# SPI-i2c-PWM_--v1.net
KiCad netlist of a schematic drawn in EAGLE
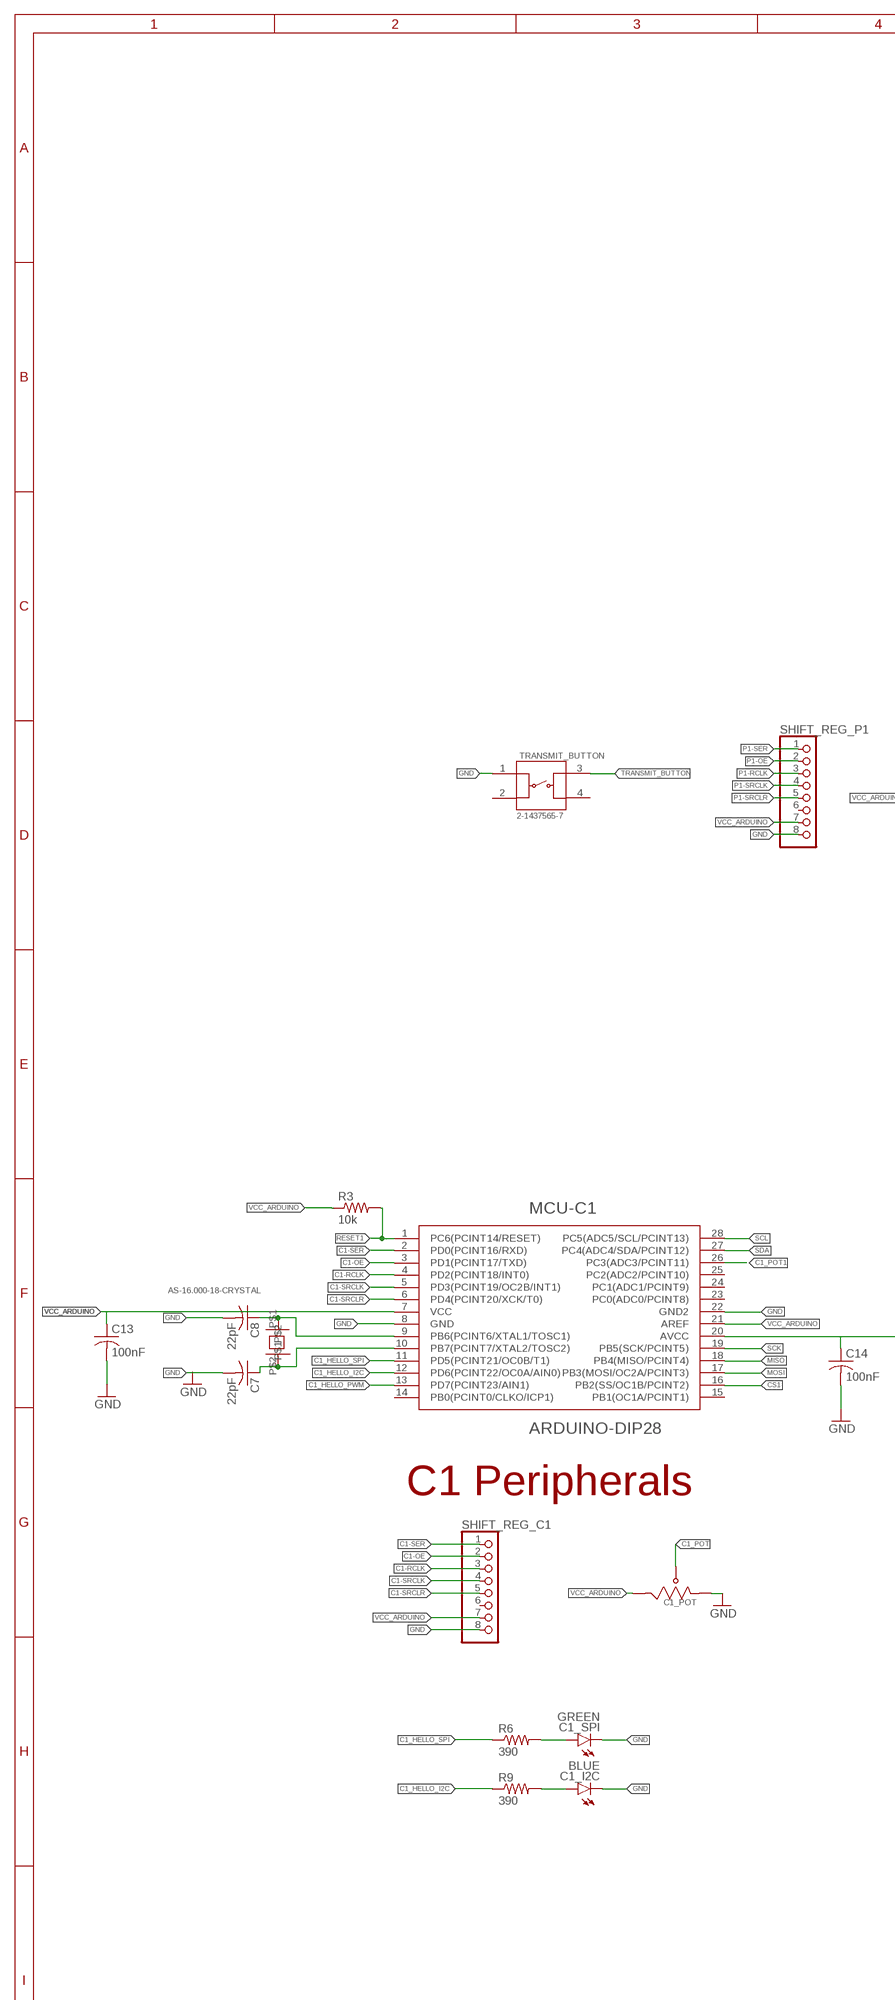
[diagram p0: schematic, sheet 1, part 1 of 2]
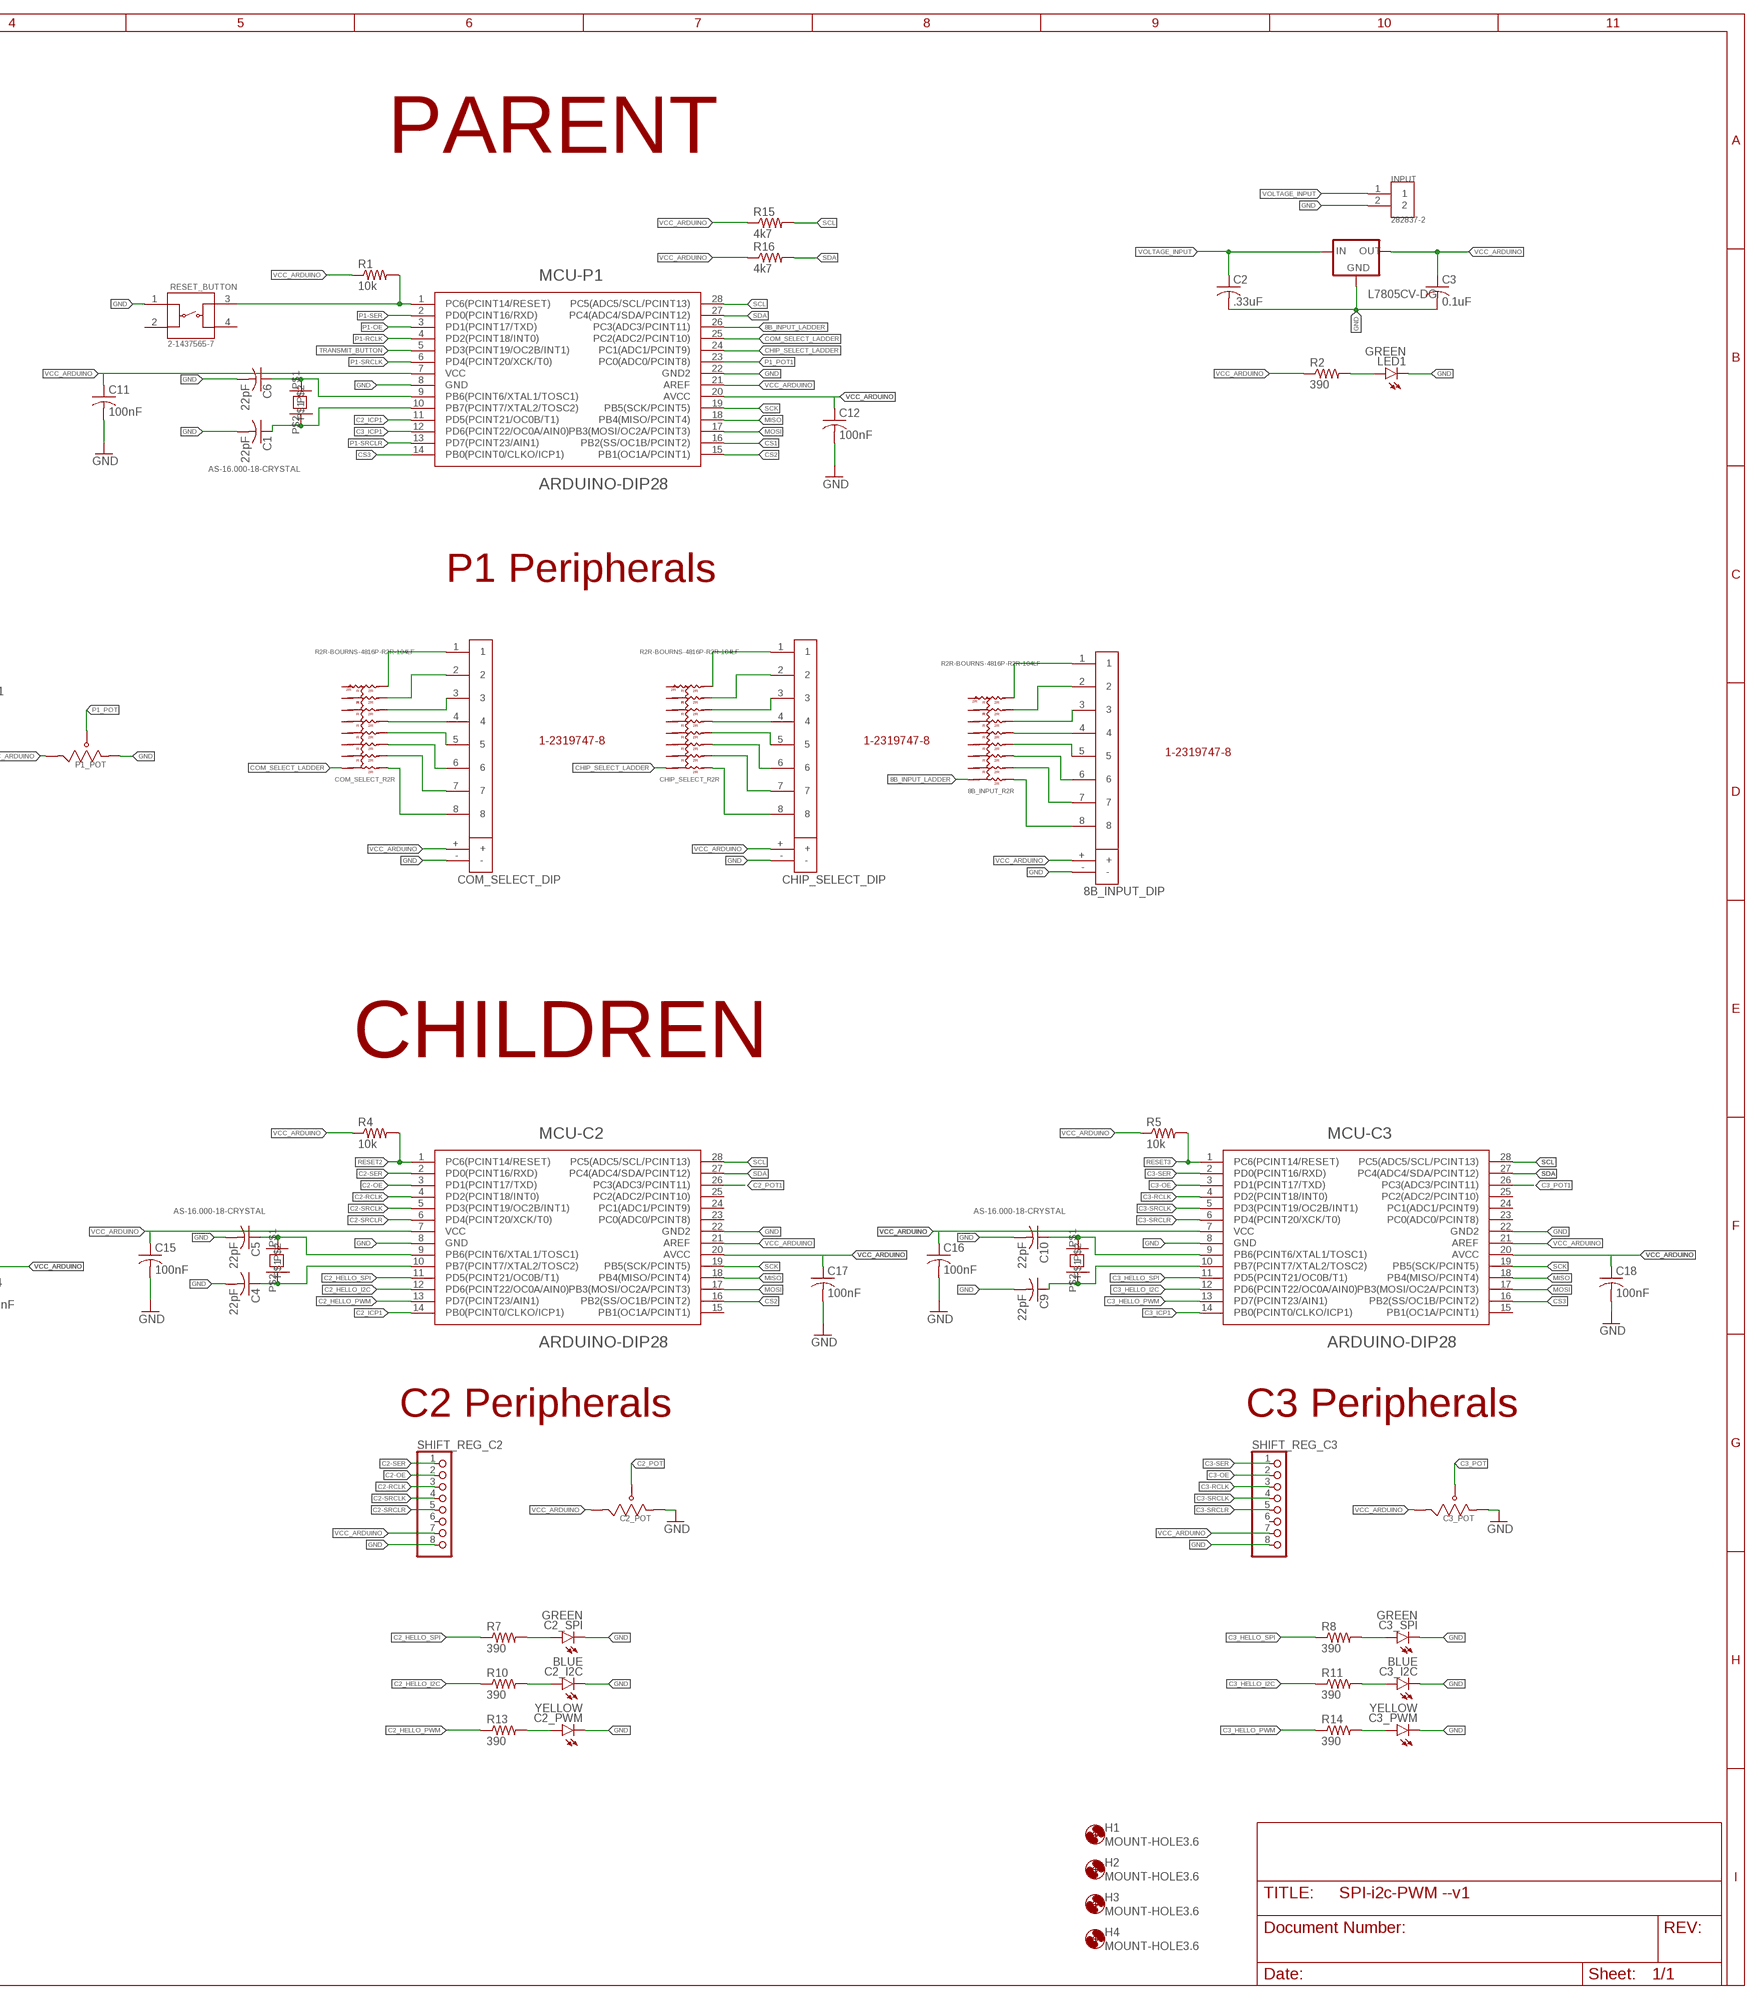
[diagram p1: schematic, sheet 1, part 2 of 2]

(export (version "E")
  (design (tool "Eeschema 10.0.6"))
  (components
    (comp (ref "5V_REG")
      (value "L7805CV-DG")
      (footprint "eagle-import:78XXS")
      (libsource (lib "eagle-import") (part "78XXS"))
    )
    (comp (ref "8B_INPUT_DIP")
      (value "DIP8-TE")
      (footprint "eagle-import:DIP8-TE(1-2319747-8)")
      (libsource (lib "eagle-import") (part "DIP8-TE"))
    )
    (comp (ref "8B_INPUT_R2R")
      (value "R2R-BOURNS-4816P-R2R-104LF")
      (footprint "eagle-import:R2RLADDER")
      (libsource (lib "eagle-import") (part "R2R-BOURNS-4816P-R2R-104LF"))
    )
    (comp (ref "C1")
      (value "22pF")
      (footprint "eagle-import:C0805")
      (libsource (lib "eagle-import") (part "C-USC0805"))
    )
    (comp (ref "C1_I2C")
      (value "BLUE")
      (footprint "eagle-import:CHIP-LED0805")
      (libsource (lib "eagle-import") (part "LEDCHIP-LED0805"))
    )
    (comp (ref "C1_POT")
      (value "POTENTIOMETER-ALLIE")
      (footprint "eagle-import:POT-ALLIEEXPRESS")
      (libsource (lib "eagle-import") (part "POTENTIOMETER-ALLIE"))
    )
    (comp (ref "C1_SPI")
      (value "GREEN")
      (footprint "eagle-import:CHIP-LED0805")
      (libsource (lib "eagle-import") (part "LEDCHIP-LED0805"))
    )
    (comp (ref "C2")
      (value ".33uF")
      (footprint "eagle-import:C0805")
      (libsource (lib "eagle-import") (part "C-USC0805"))
    )
    (comp (ref "C2_I2C")
      (value "BLUE")
      (footprint "eagle-import:CHIP-LED0805")
      (libsource (lib "eagle-import") (part "LEDCHIP-LED0805"))
    )
    (comp (ref "C2_POT")
      (value "POTENTIOMETER-ALLIE")
      (footprint "eagle-import:POT-ALLIEEXPRESS")
      (libsource (lib "eagle-import") (part "POTENTIOMETER-ALLIE"))
    )
    (comp (ref "C2_PWM")
      (value "YELLOW")
      (footprint "eagle-import:CHIP-LED0805")
      (libsource (lib "eagle-import") (part "LEDCHIP-LED0805"))
    )
    (comp (ref "C2_SPI")
      (value "GREEN")
      (footprint "eagle-import:CHIP-LED0805")
      (libsource (lib "eagle-import") (part "LEDCHIP-LED0805"))
    )
    (comp (ref "C3")
      (value "0.1uF")
      (footprint "eagle-import:C0805")
      (libsource (lib "eagle-import") (part "C-USC0805"))
    )
    (comp (ref "C3_I2C")
      (value "BLUE")
      (footprint "eagle-import:CHIP-LED0805")
      (libsource (lib "eagle-import") (part "LEDCHIP-LED0805"))
    )
    (comp (ref "C3_POT")
      (value "POTENTIOMETER-ALLIE")
      (footprint "eagle-import:POT-ALLIEEXPRESS")
      (libsource (lib "eagle-import") (part "POTENTIOMETER-ALLIE"))
    )
    (comp (ref "C3_PWM")
      (value "YELLOW")
      (footprint "eagle-import:CHIP-LED0805")
      (libsource (lib "eagle-import") (part "LEDCHIP-LED0805"))
    )
    (comp (ref "C3_SPI")
      (value "GREEN")
      (footprint "eagle-import:CHIP-LED0805")
      (libsource (lib "eagle-import") (part "LEDCHIP-LED0805"))
    )
    (comp (ref "C4")
      (value "22pF")
      (footprint "eagle-import:C0805")
      (libsource (lib "eagle-import") (part "C-USC0805"))
    )
    (comp (ref "C5")
      (value "22pF")
      (footprint "eagle-import:C0805")
      (libsource (lib "eagle-import") (part "C-USC0805"))
    )
    (comp (ref "C6")
      (value "22pF")
      (footprint "eagle-import:C0805")
      (libsource (lib "eagle-import") (part "C-USC0805"))
    )
    (comp (ref "C7")
      (value "22pF")
      (footprint "eagle-import:C0805")
      (libsource (lib "eagle-import") (part "C-USC0805"))
    )
    (comp (ref "C8")
      (value "22pF")
      (footprint "eagle-import:C0805")
      (libsource (lib "eagle-import") (part "C-USC0805"))
    )
    (comp (ref "C9")
      (value "22pF")
      (footprint "eagle-import:C0805")
      (libsource (lib "eagle-import") (part "C-USC0805"))
    )
    (comp (ref "C10")
      (value "22pF")
      (footprint "eagle-import:C0805")
      (libsource (lib "eagle-import") (part "C-USC0805"))
    )
    (comp (ref "C11")
      (value "100nF")
      (footprint "eagle-import:C0805")
      (libsource (lib "eagle-import") (part "C-USC0805"))
    )
    (comp (ref "C12")
      (value "100nF")
      (footprint "eagle-import:C0805")
      (libsource (lib "eagle-import") (part "C-USC0805"))
    )
    (comp (ref "C13")
      (value "100nF")
      (footprint "eagle-import:C0805")
      (libsource (lib "eagle-import") (part "C-USC0805"))
    )
    (comp (ref "C14")
      (value "100nF")
      (footprint "eagle-import:C0805")
      (libsource (lib "eagle-import") (part "C-USC0805"))
    )
    (comp (ref "C15")
      (value "100nF")
      (footprint "eagle-import:C0805")
      (libsource (lib "eagle-import") (part "C-USC0805"))
    )
    (comp (ref "C16")
      (value "100nF")
      (footprint "eagle-import:C0805")
      (libsource (lib "eagle-import") (part "C-USC0805"))
    )
    (comp (ref "C17")
      (value "100nF")
      (footprint "eagle-import:C0805")
      (libsource (lib "eagle-import") (part "C-USC0805"))
    )
    (comp (ref "C18")
      (value "100nF")
      (footprint "eagle-import:C0805")
      (libsource (lib "eagle-import") (part "C-USC0805"))
    )
    (comp (ref "CHIP_SELECT_DIP")
      (value "DIP8-TE")
      (footprint "eagle-import:DIP8-TE(1-2319747-8)")
      (libsource (lib "eagle-import") (part "DIP8-TE"))
    )
    (comp (ref "CHIP_SELECT_R2R")
      (value "R2R-BOURNS-4816P-R2R-104LF")
      (footprint "eagle-import:R2RLADDER")
      (libsource (lib "eagle-import") (part "R2R-BOURNS-4816P-R2R-104LF"))
    )
    (comp (ref "COM_SELECT_DIP")
      (value "DIP8-TE")
      (footprint "eagle-import:DIP8-TE(1-2319747-8)")
      (libsource (lib "eagle-import") (part "DIP8-TE"))
    )
    (comp (ref "COM_SELECT_R2R")
      (value "R2R-BOURNS-4816P-R2R-104LF")
      (footprint "eagle-import:R2RLADDER")
      (libsource (lib "eagle-import") (part "R2R-BOURNS-4816P-R2R-104LF"))
    )
    (comp (ref "H1")
      (value "MOUNT-HOLE3.6")
      (footprint "eagle-import:3,6")
      (libsource (lib "eagle-import") (part "MOUNT-HOLE3.6"))
    )
    (comp (ref "H2")
      (value "MOUNT-HOLE3.6")
      (footprint "eagle-import:3,6")
      (libsource (lib "eagle-import") (part "MOUNT-HOLE3.6"))
    )
    (comp (ref "H3")
      (value "MOUNT-HOLE3.6")
      (footprint "eagle-import:3,6")
      (libsource (lib "eagle-import") (part "MOUNT-HOLE3.6"))
    )
    (comp (ref "H4")
      (value "MOUNT-HOLE3.6")
      (footprint "eagle-import:3,6")
      (libsource (lib "eagle-import") (part "MOUNT-HOLE3.6"))
    )
    (comp (ref "INPUT")
      (value "282837-2")
      (footprint "eagle-import:TE_282837-2")
      (fields (field (name "MF") "On Shore") (field (name "MP") "OSTTE020104"))
      (libsource (lib "eagle-import") (part "282837-2"))
    )
    (comp (ref "LED1")
      (value "GREEN")
      (footprint "eagle-import:CHIPLED_0805")
      (libsource (lib "eagle-import") (part "LEDCHIPLED_0805"))
    )
    (comp (ref "M1_OSC")
      (value "AS-16.000-18-CRYSTAL")
      (footprint "eagle-import:AS-16.000-18-CRYSTAL")
      (libsource (lib "eagle-import") (part "AS-16.000-18-CRYSTAL"))
    )
    (comp (ref "MCU-C1")
      (value "ARDUINO-DIP28")
      (footprint "eagle-import:DIL28-3")
      (libsource (lib "eagle-import") (part "ARDUINO-DIP28"))
    )
    (comp (ref "MCU-C2")
      (value "ARDUINO-DIP28")
      (footprint "eagle-import:DIL28-3")
      (libsource (lib "eagle-import") (part "ARDUINO-DIP28"))
    )
    (comp (ref "MCU-C3")
      (value "ARDUINO-DIP28")
      (footprint "eagle-import:DIL28-3")
      (libsource (lib "eagle-import") (part "ARDUINO-DIP28"))
    )
    (comp (ref "MCU-P1")
      (value "ARDUINO-DIP28")
      (footprint "eagle-import:DIL28-3")
      (libsource (lib "eagle-import") (part "ARDUINO-DIP28"))
    )
    (comp (ref "P1_POT")
      (value "POTENTIOMETER-ALLIE")
      (footprint "eagle-import:POT-ALLIEEXPRESS")
      (libsource (lib "eagle-import") (part "POTENTIOMETER-ALLIE"))
    )
    (comp (ref "R1")
      (value "10k")
      (footprint "eagle-import:M0805")
      (libsource (lib "eagle-import") (part "R-US_M0805"))
    )
    (comp (ref "R2")
      (value "390")
      (footprint "eagle-import:R0805")
      (libsource (lib "eagle-import") (part "R-US_R0805"))
    )
    (comp (ref "R3")
      (value "10k")
      (footprint "eagle-import:M0805")
      (libsource (lib "eagle-import") (part "R-US_M0805"))
    )
    (comp (ref "R4")
      (value "10k")
      (footprint "eagle-import:M0805")
      (libsource (lib "eagle-import") (part "R-US_M0805"))
    )
    (comp (ref "R5")
      (value "10k")
      (footprint "eagle-import:M0805")
      (libsource (lib "eagle-import") (part "R-US_M0805"))
    )
    (comp (ref "R6")
      (value "390")
      (footprint "eagle-import:M0805")
      (libsource (lib "eagle-import") (part "R-US_M0805"))
    )
    (comp (ref "R7")
      (value "390")
      (footprint "eagle-import:M0805")
      (libsource (lib "eagle-import") (part "R-US_M0805"))
    )
    (comp (ref "R8")
      (value "390")
      (footprint "eagle-import:M0805")
      (libsource (lib "eagle-import") (part "R-US_M0805"))
    )
    (comp (ref "R9")
      (value "390")
      (footprint "eagle-import:M0805")
      (libsource (lib "eagle-import") (part "R-US_M0805"))
    )
    (comp (ref "R10")
      (value "390")
      (footprint "eagle-import:M0805")
      (libsource (lib "eagle-import") (part "R-US_M0805"))
    )
    (comp (ref "R11")
      (value "390")
      (footprint "eagle-import:M0805")
      (libsource (lib "eagle-import") (part "R-US_M0805"))
    )
    (comp (ref "R13")
      (value "390")
      (footprint "eagle-import:M0805")
      (libsource (lib "eagle-import") (part "R-US_M0805"))
    )
    (comp (ref "R14")
      (value "390")
      (footprint "eagle-import:M0805")
      (libsource (lib "eagle-import") (part "R-US_M0805"))
    )
    (comp (ref "R15")
      (value "4k7")
      (footprint "eagle-import:R0805")
      (libsource (lib "eagle-import") (part "R-US_R0805"))
    )
    (comp (ref "R16")
      (value "4k7")
      (footprint "eagle-import:R0805")
      (libsource (lib "eagle-import") (part "R-US_R0805"))
    )
    (comp (ref "RESET_BUTTON")
      (value "2-1437565-7")
      (footprint "eagle-import:SW_2-1437565-7")
      (fields (field (name "MANUFACTURER") "TE Connectivity"))
      (libsource (lib "eagle-import") (part "2-1437565-7"))
    )
    (comp (ref "S1_OSC")
      (value "AS-16.000-18-CRYSTAL")
      (footprint "eagle-import:AS-16.000-18-CRYSTAL")
      (libsource (lib "eagle-import") (part "AS-16.000-18-CRYSTAL"))
    )
    (comp (ref "S2_OSC")
      (value "AS-16.000-18-CRYSTAL")
      (footprint "eagle-import:AS-16.000-18-CRYSTAL")
      (libsource (lib "eagle-import") (part "AS-16.000-18-CRYSTAL"))
    )
    (comp (ref "S3_OSC")
      (value "AS-16.000-18-CRYSTAL")
      (footprint "eagle-import:AS-16.000-18-CRYSTAL")
      (libsource (lib "eagle-import") (part "AS-16.000-18-CRYSTAL"))
    )
    (comp (ref "SHIFT_REG_C1")
      (value "PINHD-1X8")
      (footprint "eagle-import:1X08")
      (libsource (lib "eagle-import") (part "PINHD-1X8"))
    )
    (comp (ref "SHIFT_REG_C2")
      (value "PINHD-1X8")
      (footprint "eagle-import:1X08")
      (libsource (lib "eagle-import") (part "PINHD-1X8"))
    )
    (comp (ref "SHIFT_REG_C3")
      (value "PINHD-1X8")
      (footprint "eagle-import:1X08")
      (libsource (lib "eagle-import") (part "PINHD-1X8"))
    )
    (comp (ref "SHIFT_REG_P1")
      (value "PINHD-1X8")
      (footprint "eagle-import:1X08")
      (libsource (lib "eagle-import") (part "PINHD-1X8"))
    )
    (comp (ref "TRANSMIT_BUTTON")
      (value "2-1437565-7")
      (footprint "eagle-import:SW_2-1437565-7")
      (fields (field (name "MANUFACTURER") "TE Connectivity"))
      (libsource (lib "eagle-import") (part "2-1437565-7"))
    )
  )
  (nets
    (net (code "1") (name "8B_INPUT_LADDER") (class "Default")
      (node (ref "8B_INPUT_R2R") (pin "16") (pinfunction "16_16") (pintype "bidirectional"))
      (node (ref "MCU-P1") (pin "26") (pinfunction "PC3(ADC3/PCINT11)_26") (pintype "bidirectional"))
    )
    (net (code "2") (name "C1-OE") (class "Default")
      (node (ref "MCU-C1") (pin "3") (pinfunction "PD1(PCINT17/TXD)_3") (pintype "bidirectional"))
      (node (ref "SHIFT_REG_C1") (pin "2") (pinfunction "2_2") (pintype "passive"))
    )
    (net (code "3") (name "C1-RCLK") (class "Default")
      (node (ref "MCU-C1") (pin "4") (pinfunction "PD2(PCINT18/INT0)_4") (pintype "bidirectional"))
      (node (ref "SHIFT_REG_C1") (pin "3") (pinfunction "3_3") (pintype "passive"))
    )
    (net (code "4") (name "C1-SER") (class "Default")
      (node (ref "MCU-C1") (pin "2") (pinfunction "PD0(PCINT16/RXD)_2") (pintype "bidirectional"))
      (node (ref "SHIFT_REG_C1") (pin "1") (pinfunction "1_1") (pintype "passive"))
    )
    (net (code "5") (name "C1-SRCLK") (class "Default")
      (node (ref "MCU-C1") (pin "5") (pinfunction "PD3(PCINT19/OC2B/INT1)_5") (pintype "bidirectional"))
      (node (ref "SHIFT_REG_C1") (pin "4") (pinfunction "4_4") (pintype "passive"))
    )
    (net (code "6") (name "C1-SRCLR") (class "Default")
      (node (ref "MCU-C1") (pin "6") (pinfunction "PD4(PCINT20/XCK/T0)_6") (pintype "bidirectional"))
      (node (ref "SHIFT_REG_C1") (pin "5") (pinfunction "5_5") (pintype "passive"))
    )
    (net (code "7") (name "C1_HELLO_I2C") (class "Default")
      (node (ref "MCU-C1") (pin "12") (pinfunction "PD6(PCINT22/OC0A/AIN0)_12") (pintype "bidirectional"))
      (node (ref "R9") (pin "1") (pinfunction "1_1") (pintype "passive"))
    )
    (net (code "8") (name "C1_HELLO_PWM") (class "Default")
      (node (ref "MCU-C1") (pin "13") (pinfunction "PD7(PCINT23/AIN1)_13") (pintype "bidirectional"))
    )
    (net (code "9") (name "C1_HELLO_SPI") (class "Default")
      (node (ref "MCU-C1") (pin "11") (pinfunction "PD5(PCINT21/OC0B/T1)_11") (pintype "bidirectional"))
      (node (ref "R6") (pin "1") (pinfunction "1_1") (pintype "passive"))
    )
    (net (code "10") (name "C1_POT") (class "Default")
      (node (ref "C1_POT") (pin "P$2") (pinfunction "P$2_P$2") (pintype "bidirectional"))
    )
    (net (code "11") (name "C1_POT1") (class "Default")
      (node (ref "MCU-C1") (pin "26") (pinfunction "PC3(ADC3/PCINT11)_26") (pintype "bidirectional"))
    )
    (net (code "12") (name "C2-OE") (class "Default")
      (node (ref "MCU-C2") (pin "3") (pinfunction "PD1(PCINT17/TXD)_3") (pintype "bidirectional"))
      (node (ref "SHIFT_REG_C2") (pin "2") (pinfunction "2_2") (pintype "passive"))
    )
    (net (code "13") (name "C2-RCLK") (class "Default")
      (node (ref "MCU-C2") (pin "4") (pinfunction "PD2(PCINT18/INT0)_4") (pintype "bidirectional"))
      (node (ref "SHIFT_REG_C2") (pin "3") (pinfunction "3_3") (pintype "passive"))
    )
    (net (code "14") (name "C2-SER") (class "Default")
      (node (ref "MCU-C2") (pin "2") (pinfunction "PD0(PCINT16/RXD)_2") (pintype "bidirectional"))
      (node (ref "SHIFT_REG_C2") (pin "1") (pinfunction "1_1") (pintype "passive"))
    )
    (net (code "15") (name "C2-SRCLK") (class "Default")
      (node (ref "MCU-C2") (pin "5") (pinfunction "PD3(PCINT19/OC2B/INT1)_5") (pintype "bidirectional"))
      (node (ref "SHIFT_REG_C2") (pin "4") (pinfunction "4_4") (pintype "passive"))
    )
    (net (code "16") (name "C2-SRCLR") (class "Default")
      (node (ref "MCU-C2") (pin "6") (pinfunction "PD4(PCINT20/XCK/T0)_6") (pintype "bidirectional"))
      (node (ref "SHIFT_REG_C2") (pin "5") (pinfunction "5_5") (pintype "passive"))
    )
    (net (code "17") (name "C2_HELLO_I2C") (class "Default")
      (node (ref "MCU-C2") (pin "12") (pinfunction "PD6(PCINT22/OC0A/AIN0)_12") (pintype "bidirectional"))
      (node (ref "R10") (pin "1") (pinfunction "1_1") (pintype "passive"))
    )
    (net (code "18") (name "C2_HELLO_PWM") (class "Default")
      (node (ref "MCU-C2") (pin "13") (pinfunction "PD7(PCINT23/AIN1)_13") (pintype "bidirectional"))
      (node (ref "R13") (pin "1") (pinfunction "1_1") (pintype "passive"))
    )
    (net (code "19") (name "C2_HELLO_SPI") (class "Default")
      (node (ref "MCU-C2") (pin "11") (pinfunction "PD5(PCINT21/OC0B/T1)_11") (pintype "bidirectional"))
      (node (ref "R7") (pin "1") (pinfunction "1_1") (pintype "passive"))
    )
    (net (code "20") (name "C2_ICP1") (class "Default")
      (node (ref "MCU-C2") (pin "14") (pinfunction "PB0(PCINT0/CLKO/ICP1)_14") (pintype "bidirectional"))
      (node (ref "MCU-P1") (pin "11") (pinfunction "PD5(PCINT21/OC0B/T1)_11") (pintype "bidirectional"))
    )
    (net (code "21") (name "C2_POT") (class "Default")
      (node (ref "C2_POT") (pin "P$2") (pinfunction "P$2_P$2") (pintype "bidirectional"))
    )
    (net (code "22") (name "C2_POT1") (class "Default")
      (node (ref "MCU-C2") (pin "26") (pinfunction "PC3(ADC3/PCINT11)_26") (pintype "bidirectional"))
    )
    (net (code "23") (name "C3-OE") (class "Default")
      (node (ref "MCU-C3") (pin "3") (pinfunction "PD1(PCINT17/TXD)_3") (pintype "bidirectional"))
      (node (ref "SHIFT_REG_C3") (pin "2") (pinfunction "2_2") (pintype "passive"))
    )
    (net (code "24") (name "C3-RCLK") (class "Default")
      (node (ref "MCU-C3") (pin "4") (pinfunction "PD2(PCINT18/INT0)_4") (pintype "bidirectional"))
      (node (ref "SHIFT_REG_C3") (pin "3") (pinfunction "3_3") (pintype "passive"))
    )
    (net (code "25") (name "C3-SER") (class "Default")
      (node (ref "MCU-C3") (pin "2") (pinfunction "PD0(PCINT16/RXD)_2") (pintype "bidirectional"))
      (node (ref "SHIFT_REG_C3") (pin "1") (pinfunction "1_1") (pintype "passive"))
    )
    (net (code "26") (name "C3-SRCLK") (class "Default")
      (node (ref "MCU-C3") (pin "5") (pinfunction "PD3(PCINT19/OC2B/INT1)_5") (pintype "bidirectional"))
      (node (ref "SHIFT_REG_C3") (pin "4") (pinfunction "4_4") (pintype "passive"))
    )
    (net (code "27") (name "C3-SRCLR") (class "Default")
      (node (ref "MCU-C3") (pin "6") (pinfunction "PD4(PCINT20/XCK/T0)_6") (pintype "bidirectional"))
      (node (ref "SHIFT_REG_C3") (pin "5") (pinfunction "5_5") (pintype "passive"))
    )
    (net (code "28") (name "C3_HELLO_I2C") (class "Default")
      (node (ref "MCU-C3") (pin "12") (pinfunction "PD6(PCINT22/OC0A/AIN0)_12") (pintype "bidirectional"))
      (node (ref "R11") (pin "1") (pinfunction "1_1") (pintype "passive"))
    )
    (net (code "29") (name "C3_HELLO_PWM") (class "Default")
      (node (ref "MCU-C3") (pin "13") (pinfunction "PD7(PCINT23/AIN1)_13") (pintype "bidirectional"))
      (node (ref "R14") (pin "1") (pinfunction "1_1") (pintype "passive"))
    )
    (net (code "30") (name "C3_HELLO_SPI") (class "Default")
      (node (ref "MCU-C3") (pin "11") (pinfunction "PD5(PCINT21/OC0B/T1)_11") (pintype "bidirectional"))
      (node (ref "R8") (pin "1") (pinfunction "1_1") (pintype "passive"))
    )
    (net (code "31") (name "C3_ICP1") (class "Default")
      (node (ref "MCU-C3") (pin "14") (pinfunction "PB0(PCINT0/CLKO/ICP1)_14") (pintype "bidirectional"))
      (node (ref "MCU-P1") (pin "12") (pinfunction "PD6(PCINT22/OC0A/AIN0)_12") (pintype "bidirectional"))
    )
    (net (code "32") (name "C3_POT") (class "Default")
      (node (ref "C3_POT") (pin "P$2") (pinfunction "P$2_P$2") (pintype "bidirectional"))
    )
    (net (code "33") (name "C3_POT1") (class "Default")
      (node (ref "MCU-C3") (pin "26") (pinfunction "PC3(ADC3/PCINT11)_26") (pintype "bidirectional"))
    )
    (net (code "34") (name "CHIP_SELECT_LADDER") (class "Default")
      (node (ref "CHIP_SELECT_R2R") (pin "16") (pinfunction "16_16") (pintype "bidirectional"))
      (node (ref "MCU-P1") (pin "24") (pinfunction "PC1(ADC1/PCINT9)_24") (pintype "bidirectional"))
    )
    (net (code "35") (name "COM_SELECT_LADDER") (class "Default")
      (node (ref "COM_SELECT_R2R") (pin "16") (pinfunction "16_16") (pintype "bidirectional"))
      (node (ref "MCU-P1") (pin "25") (pinfunction "PC2(ADC2/PCINT10)_25") (pintype "bidirectional"))
    )
    (net (code "36") (name "CS1") (class "Default")
      (node (ref "MCU-C1") (pin "16") (pinfunction "PB2(SS/OC1B/PCINT2)_16") (pintype "bidirectional"))
      (node (ref "MCU-P1") (pin "16") (pinfunction "PB2(SS/OC1B/PCINT2)_16") (pintype "bidirectional"))
    )
    (net (code "37") (name "CS2") (class "Default")
      (node (ref "MCU-C2") (pin "16") (pinfunction "PB2(SS/OC1B/PCINT2)_16") (pintype "bidirectional"))
      (node (ref "MCU-P1") (pin "15") (pinfunction "PB1(OC1A/PCINT1)_15") (pintype "bidirectional"))
    )
    (net (code "38") (name "CS3") (class "Default")
      (node (ref "MCU-C3") (pin "16") (pinfunction "PB2(SS/OC1B/PCINT2)_16") (pintype "bidirectional"))
      (node (ref "MCU-P1") (pin "14") (pinfunction "PB0(PCINT0/CLKO/ICP1)_14") (pintype "bidirectional"))
    )
    (net (code "39") (name "GND") (class "Default")
      (node (ref "5V_REG") (pin "GND") (pinfunction "GND_GND") (pintype "input"))
      (node (ref "8B_INPUT_DIP") (pin "-") (pinfunction "-_-") (pintype "bidirectional"))
      (node (ref "C1") (pin "2") (pinfunction "2_2") (pintype "passive"))
      (node (ref "C10") (pin "2") (pinfunction "2_2") (pintype "passive"))
      (node (ref "C11") (pin "2") (pinfunction "2_2") (pintype "passive"))
      (node (ref "C12") (pin "2") (pinfunction "2_2") (pintype "passive"))
      (node (ref "C13") (pin "2") (pinfunction "2_2") (pintype "passive"))
      (node (ref "C14") (pin "2") (pinfunction "2_2") (pintype "passive"))
      (node (ref "C15") (pin "2") (pinfunction "2_2") (pintype "passive"))
      (node (ref "C16") (pin "2") (pinfunction "2_2") (pintype "passive"))
      (node (ref "C17") (pin "2") (pinfunction "2_2") (pintype "passive"))
      (node (ref "C18") (pin "2") (pinfunction "2_2") (pintype "passive"))
      (node (ref "C1_I2C") (pin "C") (pinfunction "C_C") (pintype "passive"))
      (node (ref "C1_POT") (pin "P$3") (pinfunction "P$3_P$3") (pintype "bidirectional"))
      (node (ref "C1_SPI") (pin "C") (pinfunction "C_C") (pintype "passive"))
      (node (ref "C2") (pin "2") (pinfunction "2_2") (pintype "passive"))
      (node (ref "C2_I2C") (pin "C") (pinfunction "C_C") (pintype "passive"))
      (node (ref "C2_POT") (pin "P$3") (pinfunction "P$3_P$3") (pintype "bidirectional"))
      (node (ref "C2_PWM") (pin "C") (pinfunction "C_C") (pintype "passive"))
      (node (ref "C2_SPI") (pin "C") (pinfunction "C_C") (pintype "passive"))
      (node (ref "C3") (pin "2") (pinfunction "2_2") (pintype "passive"))
      (node (ref "C3_I2C") (pin "C") (pinfunction "C_C") (pintype "passive"))
      (node (ref "C3_POT") (pin "P$3") (pinfunction "P$3_P$3") (pintype "bidirectional"))
      (node (ref "C3_PWM") (pin "C") (pinfunction "C_C") (pintype "passive"))
      (node (ref "C3_SPI") (pin "C") (pinfunction "C_C") (pintype "passive"))
      (node (ref "C4") (pin "2") (pinfunction "2_2") (pintype "passive"))
      (node (ref "C5") (pin "2") (pinfunction "2_2") (pintype "passive"))
      (node (ref "C6") (pin "2") (pinfunction "2_2") (pintype "passive"))
      (node (ref "C7") (pin "2") (pinfunction "2_2") (pintype "passive"))
      (node (ref "C8") (pin "2") (pinfunction "2_2") (pintype "passive"))
      (node (ref "C9") (pin "2") (pinfunction "2_2") (pintype "passive"))
      (node (ref "CHIP_SELECT_DIP") (pin "-") (pinfunction "-_-") (pintype "bidirectional"))
      (node (ref "COM_SELECT_DIP") (pin "-") (pinfunction "-_-") (pintype "bidirectional"))
      (node (ref "INPUT") (pin "2") (pinfunction "2_2") (pintype "passive"))
      (node (ref "LED1") (pin "C") (pinfunction "C_C") (pintype "passive"))
      (node (ref "MCU-C1") (pin "22") (pinfunction "GND2_22") (pintype "bidirectional"))
      (node (ref "MCU-C1") (pin "8") (pinfunction "GND_8") (pintype "bidirectional"))
      (node (ref "MCU-C2") (pin "22") (pinfunction "GND2_22") (pintype "bidirectional"))
      (node (ref "MCU-C2") (pin "8") (pinfunction "GND_8") (pintype "bidirectional"))
      (node (ref "MCU-C3") (pin "22") (pinfunction "GND2_22") (pintype "bidirectional"))
      (node (ref "MCU-C3") (pin "8") (pinfunction "GND_8") (pintype "bidirectional"))
      (node (ref "MCU-P1") (pin "22") (pinfunction "GND2_22") (pintype "bidirectional"))
      (node (ref "MCU-P1") (pin "8") (pinfunction "GND_8") (pintype "bidirectional"))
      (node (ref "P1_POT") (pin "P$3") (pinfunction "P$3_P$3") (pintype "bidirectional"))
      (node (ref "RESET_BUTTON") (pin "1") (pinfunction "1_1") (pintype "passive"))
      (node (ref "SHIFT_REG_C1") (pin "8") (pinfunction "8_8") (pintype "passive"))
      (node (ref "SHIFT_REG_C2") (pin "8") (pinfunction "8_8") (pintype "passive"))
      (node (ref "SHIFT_REG_C3") (pin "8") (pinfunction "8_8") (pintype "passive"))
      (node (ref "SHIFT_REG_P1") (pin "8") (pinfunction "8_8") (pintype "passive"))
      (node (ref "TRANSMIT_BUTTON") (pin "1") (pinfunction "1_1") (pintype "passive"))
    )
    (net (code "40") (name "MISO") (class "Default")
      (node (ref "MCU-C1") (pin "18") (pinfunction "PB4(MISO/PCINT4)_18") (pintype "bidirectional"))
      (node (ref "MCU-C2") (pin "18") (pinfunction "PB4(MISO/PCINT4)_18") (pintype "bidirectional"))
      (node (ref "MCU-C3") (pin "18") (pinfunction "PB4(MISO/PCINT4)_18") (pintype "bidirectional"))
      (node (ref "MCU-P1") (pin "18") (pinfunction "PB4(MISO/PCINT4)_18") (pintype "bidirectional"))
    )
    (net (code "41") (name "MOSI") (class "Default")
      (node (ref "MCU-C1") (pin "17") (pinfunction "PB3(MOSI/OC2A/PCINT3)_17") (pintype "bidirectional"))
      (node (ref "MCU-C2") (pin "17") (pinfunction "PB3(MOSI/OC2A/PCINT3)_17") (pintype "bidirectional"))
      (node (ref "MCU-C3") (pin "17") (pinfunction "PB3(MOSI/OC2A/PCINT3)_17") (pintype "bidirectional"))
      (node (ref "MCU-P1") (pin "17") (pinfunction "PB3(MOSI/OC2A/PCINT3)_17") (pintype "bidirectional"))
    )
    (net (code "42") (name "Net-(8B_INPUT_DIP-Pad1)") (class "Default")
      (node (ref "8B_INPUT_DIP") (pin "1") (pinfunction "1_1") (pintype "bidirectional"))
      (node (ref "8B_INPUT_R2R") (pin "8") (pinfunction "8_8") (pintype "bidirectional"))
    )
    (net (code "43") (name "Net-(8B_INPUT_DIP-Pad2)") (class "Default")
      (node (ref "8B_INPUT_DIP") (pin "2") (pinfunction "2_2") (pintype "bidirectional"))
      (node (ref "8B_INPUT_R2R") (pin "7") (pinfunction "7_7") (pintype "bidirectional"))
    )
    (net (code "44") (name "Net-(8B_INPUT_DIP-Pad3)") (class "Default")
      (node (ref "8B_INPUT_DIP") (pin "3") (pinfunction "3_3") (pintype "bidirectional"))
      (node (ref "8B_INPUT_R2R") (pin "6") (pinfunction "6_6") (pintype "bidirectional"))
    )
    (net (code "45") (name "Net-(8B_INPUT_DIP-Pad4)") (class "Default")
      (node (ref "8B_INPUT_DIP") (pin "4") (pinfunction "4_4") (pintype "bidirectional"))
      (node (ref "8B_INPUT_R2R") (pin "5") (pinfunction "5_5") (pintype "bidirectional"))
    )
    (net (code "46") (name "Net-(8B_INPUT_DIP-Pad5)") (class "Default")
      (node (ref "8B_INPUT_DIP") (pin "5") (pinfunction "5_5") (pintype "bidirectional"))
      (node (ref "8B_INPUT_R2R") (pin "4") (pinfunction "4_4") (pintype "bidirectional"))
    )
    (net (code "47") (name "Net-(8B_INPUT_DIP-Pad6)") (class "Default")
      (node (ref "8B_INPUT_DIP") (pin "6") (pinfunction "6_6") (pintype "bidirectional"))
      (node (ref "8B_INPUT_R2R") (pin "3") (pinfunction "3_3") (pintype "bidirectional"))
    )
    (net (code "48") (name "Net-(8B_INPUT_DIP-Pad7)") (class "Default")
      (node (ref "8B_INPUT_DIP") (pin "7") (pinfunction "7_7") (pintype "bidirectional"))
      (node (ref "8B_INPUT_R2R") (pin "2") (pinfunction "2_2") (pintype "bidirectional"))
    )
    (net (code "49") (name "Net-(8B_INPUT_DIP-Pad8)") (class "Default")
      (node (ref "8B_INPUT_DIP") (pin "8") (pinfunction "8_8") (pintype "bidirectional"))
      (node (ref "8B_INPUT_R2R") (pin "1") (pinfunction "1_1") (pintype "bidirectional"))
    )
    (net (code "50") (name "Net-(C1_I2C-PadA)") (class "Default")
      (node (ref "C1_I2C") (pin "A") (pinfunction "A_A") (pintype "passive"))
      (node (ref "R9") (pin "2") (pinfunction "2_2") (pintype "passive"))
    )
    (net (code "51") (name "Net-(C1_SPI-PadA)") (class "Default")
      (node (ref "C1_SPI") (pin "A") (pinfunction "A_A") (pintype "passive"))
      (node (ref "R6") (pin "2") (pinfunction "2_2") (pintype "passive"))
    )
    (net (code "52") (name "Net-(C2_I2C-PadA)") (class "Default")
      (node (ref "C2_I2C") (pin "A") (pinfunction "A_A") (pintype "passive"))
      (node (ref "R10") (pin "2") (pinfunction "2_2") (pintype "passive"))
    )
    (net (code "53") (name "Net-(C2_PWM-PadA)") (class "Default")
      (node (ref "C2_PWM") (pin "A") (pinfunction "A_A") (pintype "passive"))
      (node (ref "R13") (pin "2") (pinfunction "2_2") (pintype "passive"))
    )
    (net (code "54") (name "Net-(C2_SPI-PadA)") (class "Default")
      (node (ref "C2_SPI") (pin "A") (pinfunction "A_A") (pintype "passive"))
      (node (ref "R7") (pin "2") (pinfunction "2_2") (pintype "passive"))
    )
    (net (code "55") (name "Net-(C3_I2C-PadA)") (class "Default")
      (node (ref "C3_I2C") (pin "A") (pinfunction "A_A") (pintype "passive"))
      (node (ref "R11") (pin "2") (pinfunction "2_2") (pintype "passive"))
    )
    (net (code "56") (name "Net-(C3_PWM-PadA)") (class "Default")
      (node (ref "C3_PWM") (pin "A") (pinfunction "A_A") (pintype "passive"))
      (node (ref "R14") (pin "2") (pinfunction "2_2") (pintype "passive"))
    )
    (net (code "57") (name "Net-(C3_SPI-PadA)") (class "Default")
      (node (ref "C3_SPI") (pin "A") (pinfunction "A_A") (pintype "passive"))
      (node (ref "R8") (pin "2") (pinfunction "2_2") (pintype "passive"))
    )
    (net (code "58") (name "Net-(CHIP_SELECT_DIP-Pad1)") (class "Default")
      (node (ref "CHIP_SELECT_DIP") (pin "1") (pinfunction "1_1") (pintype "bidirectional"))
      (node (ref "CHIP_SELECT_R2R") (pin "8") (pinfunction "8_8") (pintype "bidirectional"))
    )
    (net (code "59") (name "Net-(CHIP_SELECT_DIP-Pad2)") (class "Default")
      (node (ref "CHIP_SELECT_DIP") (pin "2") (pinfunction "2_2") (pintype "bidirectional"))
      (node (ref "CHIP_SELECT_R2R") (pin "7") (pinfunction "7_7") (pintype "bidirectional"))
    )
    (net (code "60") (name "Net-(CHIP_SELECT_DIP-Pad3)") (class "Default")
      (node (ref "CHIP_SELECT_DIP") (pin "3") (pinfunction "3_3") (pintype "bidirectional"))
      (node (ref "CHIP_SELECT_R2R") (pin "6") (pinfunction "6_6") (pintype "bidirectional"))
    )
    (net (code "61") (name "Net-(CHIP_SELECT_DIP-Pad4)") (class "Default")
      (node (ref "CHIP_SELECT_DIP") (pin "4") (pinfunction "4_4") (pintype "bidirectional"))
      (node (ref "CHIP_SELECT_R2R") (pin "5") (pinfunction "5_5") (pintype "bidirectional"))
    )
    (net (code "62") (name "Net-(CHIP_SELECT_DIP-Pad5)") (class "Default")
      (node (ref "CHIP_SELECT_DIP") (pin "5") (pinfunction "5_5") (pintype "bidirectional"))
      (node (ref "CHIP_SELECT_R2R") (pin "4") (pinfunction "4_4") (pintype "bidirectional"))
    )
    (net (code "63") (name "Net-(CHIP_SELECT_DIP-Pad6)") (class "Default")
      (node (ref "CHIP_SELECT_DIP") (pin "6") (pinfunction "6_6") (pintype "bidirectional"))
      (node (ref "CHIP_SELECT_R2R") (pin "3") (pinfunction "3_3") (pintype "bidirectional"))
    )
    (net (code "64") (name "Net-(CHIP_SELECT_DIP-Pad7)") (class "Default")
      (node (ref "CHIP_SELECT_DIP") (pin "7") (pinfunction "7_7") (pintype "bidirectional"))
      (node (ref "CHIP_SELECT_R2R") (pin "2") (pinfunction "2_2") (pintype "bidirectional"))
    )
    (net (code "65") (name "Net-(CHIP_SELECT_DIP-Pad8)") (class "Default")
      (node (ref "CHIP_SELECT_DIP") (pin "8") (pinfunction "8_8") (pintype "bidirectional"))
      (node (ref "CHIP_SELECT_R2R") (pin "1") (pinfunction "1_1") (pintype "bidirectional"))
    )
    (net (code "66") (name "Net-(COM_SELECT_DIP-Pad1)") (class "Default")
      (node (ref "COM_SELECT_DIP") (pin "1") (pinfunction "1_1") (pintype "bidirectional"))
      (node (ref "COM_SELECT_R2R") (pin "8") (pinfunction "8_8") (pintype "bidirectional"))
    )
    (net (code "67") (name "Net-(COM_SELECT_DIP-Pad2)") (class "Default")
      (node (ref "COM_SELECT_DIP") (pin "2") (pinfunction "2_2") (pintype "bidirectional"))
      (node (ref "COM_SELECT_R2R") (pin "7") (pinfunction "7_7") (pintype "bidirectional"))
    )
    (net (code "68") (name "Net-(COM_SELECT_DIP-Pad3)") (class "Default")
      (node (ref "COM_SELECT_DIP") (pin "3") (pinfunction "3_3") (pintype "bidirectional"))
      (node (ref "COM_SELECT_R2R") (pin "6") (pinfunction "6_6") (pintype "bidirectional"))
    )
    (net (code "69") (name "Net-(COM_SELECT_DIP-Pad4)") (class "Default")
      (node (ref "COM_SELECT_DIP") (pin "4") (pinfunction "4_4") (pintype "bidirectional"))
      (node (ref "COM_SELECT_R2R") (pin "5") (pinfunction "5_5") (pintype "bidirectional"))
    )
    (net (code "70") (name "Net-(COM_SELECT_DIP-Pad5)") (class "Default")
      (node (ref "COM_SELECT_DIP") (pin "5") (pinfunction "5_5") (pintype "bidirectional"))
      (node (ref "COM_SELECT_R2R") (pin "4") (pinfunction "4_4") (pintype "bidirectional"))
    )
    (net (code "71") (name "Net-(COM_SELECT_DIP-Pad6)") (class "Default")
      (node (ref "COM_SELECT_DIP") (pin "6") (pinfunction "6_6") (pintype "bidirectional"))
      (node (ref "COM_SELECT_R2R") (pin "3") (pinfunction "3_3") (pintype "bidirectional"))
    )
    (net (code "72") (name "Net-(COM_SELECT_DIP-Pad7)") (class "Default")
      (node (ref "COM_SELECT_DIP") (pin "7") (pinfunction "7_7") (pintype "bidirectional"))
      (node (ref "COM_SELECT_R2R") (pin "2") (pinfunction "2_2") (pintype "bidirectional"))
    )
    (net (code "73") (name "Net-(COM_SELECT_DIP-Pad8)") (class "Default")
      (node (ref "COM_SELECT_DIP") (pin "8") (pinfunction "8_8") (pintype "bidirectional"))
      (node (ref "COM_SELECT_R2R") (pin "1") (pinfunction "1_1") (pintype "bidirectional"))
    )
    (net (code "74") (name "Net-(LED1-PadA)") (class "Default")
      (node (ref "LED1") (pin "A") (pinfunction "A_A") (pintype "passive"))
      (node (ref "R2") (pin "2") (pinfunction "2_2") (pintype "passive"))
    )
    (net (code "75") (name "Net-(MCU-C1-PB6(PCINT6{slash}XTAL1{slash}TOSC1))") (class "Default")
      (node (ref "C8") (pin "1") (pinfunction "1_1") (pintype "passive"))
      (node (ref "MCU-C1") (pin "9") (pinfunction "PB6(PCINT6/XTAL1/TOSC1)_9") (pintype "bidirectional"))
      (node (ref "S1_OSC") (pin "P$1") (pinfunction "P$1_P$1") (pintype "bidirectional"))
    )
    (net (code "76") (name "Net-(MCU-C1-PB7(PCINT7{slash}XTAL2{slash}TOSC2))") (class "Default")
      (node (ref "C7") (pin "1") (pinfunction "1_1") (pintype "passive"))
      (node (ref "MCU-C1") (pin "10") (pinfunction "PB7(PCINT7/XTAL2/TOSC2)_10") (pintype "bidirectional"))
      (node (ref "S1_OSC") (pin "P$2") (pinfunction "P$2_P$2") (pintype "bidirectional"))
    )
    (net (code "77") (name "Net-(MCU-C2-PB6(PCINT6{slash}XTAL1{slash}TOSC1))") (class "Default")
      (node (ref "C5") (pin "1") (pinfunction "1_1") (pintype "passive"))
      (node (ref "MCU-C2") (pin "9") (pinfunction "PB6(PCINT6/XTAL1/TOSC1)_9") (pintype "bidirectional"))
      (node (ref "S2_OSC") (pin "P$1") (pinfunction "P$1_P$1") (pintype "bidirectional"))
    )
    (net (code "78") (name "Net-(MCU-C2-PB7(PCINT7{slash}XTAL2{slash}TOSC2))") (class "Default")
      (node (ref "C4") (pin "1") (pinfunction "1_1") (pintype "passive"))
      (node (ref "MCU-C2") (pin "10") (pinfunction "PB7(PCINT7/XTAL2/TOSC2)_10") (pintype "bidirectional"))
      (node (ref "S2_OSC") (pin "P$2") (pinfunction "P$2_P$2") (pintype "bidirectional"))
    )
    (net (code "79") (name "Net-(MCU-C3-PB6(PCINT6{slash}XTAL1{slash}TOSC1))") (class "Default")
      (node (ref "C10") (pin "1") (pinfunction "1_1") (pintype "passive"))
      (node (ref "MCU-C3") (pin "9") (pinfunction "PB6(PCINT6/XTAL1/TOSC1)_9") (pintype "bidirectional"))
      (node (ref "S3_OSC") (pin "P$1") (pinfunction "P$1_P$1") (pintype "bidirectional"))
    )
    (net (code "80") (name "Net-(MCU-C3-PB7(PCINT7{slash}XTAL2{slash}TOSC2))") (class "Default")
      (node (ref "C9") (pin "1") (pinfunction "1_1") (pintype "passive"))
      (node (ref "MCU-C3") (pin "10") (pinfunction "PB7(PCINT7/XTAL2/TOSC2)_10") (pintype "bidirectional"))
      (node (ref "S3_OSC") (pin "P$2") (pinfunction "P$2_P$2") (pintype "bidirectional"))
    )
    (net (code "81") (name "Net-(MCU-P1-PB6(PCINT6{slash}XTAL1{slash}TOSC1))") (class "Default")
      (node (ref "C6") (pin "1") (pinfunction "1_1") (pintype "passive"))
      (node (ref "M1_OSC") (pin "P$1") (pinfunction "P$1_P$1") (pintype "bidirectional"))
      (node (ref "MCU-P1") (pin "9") (pinfunction "PB6(PCINT6/XTAL1/TOSC1)_9") (pintype "bidirectional"))
    )
    (net (code "82") (name "Net-(MCU-P1-PB7(PCINT7{slash}XTAL2{slash}TOSC2))") (class "Default")
      (node (ref "C1") (pin "1") (pinfunction "1_1") (pintype "passive"))
      (node (ref "M1_OSC") (pin "P$2") (pinfunction "P$2_P$2") (pintype "bidirectional"))
      (node (ref "MCU-P1") (pin "10") (pinfunction "PB7(PCINT7/XTAL2/TOSC2)_10") (pintype "bidirectional"))
    )
    (net (code "83") (name "Net-(MCU-P1-PC6(PCINT14{slash}RESET))") (class "Default")
      (node (ref "MCU-P1") (pin "1") (pinfunction "PC6(PCINT14/RESET)_1") (pintype "bidirectional"))
      (node (ref "R1") (pin "2") (pinfunction "2_2") (pintype "passive"))
      (node (ref "RESET_BUTTON") (pin "3") (pinfunction "3_3") (pintype "passive"))
    )
    (net (code "84") (name "P1-OE") (class "Default")
      (node (ref "MCU-P1") (pin "3") (pinfunction "PD1(PCINT17/TXD)_3") (pintype "bidirectional"))
      (node (ref "SHIFT_REG_P1") (pin "2") (pinfunction "2_2") (pintype "passive"))
    )
    (net (code "85") (name "P1-RCLK") (class "Default")
      (node (ref "MCU-P1") (pin "4") (pinfunction "PD2(PCINT18/INT0)_4") (pintype "bidirectional"))
      (node (ref "SHIFT_REG_P1") (pin "3") (pinfunction "3_3") (pintype "passive"))
    )
    (net (code "86") (name "P1-SER") (class "Default")
      (node (ref "MCU-P1") (pin "2") (pinfunction "PD0(PCINT16/RXD)_2") (pintype "bidirectional"))
      (node (ref "SHIFT_REG_P1") (pin "1") (pinfunction "1_1") (pintype "passive"))
    )
    (net (code "87") (name "P1-SRCLK") (class "Default")
      (node (ref "MCU-P1") (pin "6") (pinfunction "PD4(PCINT20/XCK/T0)_6") (pintype "bidirectional"))
      (node (ref "SHIFT_REG_P1") (pin "4") (pinfunction "4_4") (pintype "passive"))
    )
    (net (code "88") (name "P1-SRCLR") (class "Default")
      (node (ref "MCU-P1") (pin "13") (pinfunction "PD7(PCINT23/AIN1)_13") (pintype "bidirectional"))
      (node (ref "SHIFT_REG_P1") (pin "5") (pinfunction "5_5") (pintype "passive"))
    )
    (net (code "89") (name "P1_POT") (class "Default")
      (node (ref "P1_POT") (pin "P$2") (pinfunction "P$2_P$2") (pintype "bidirectional"))
    )
    (net (code "90") (name "P1_POT1") (class "Default")
      (node (ref "MCU-P1") (pin "23") (pinfunction "PC0(ADC0/PCINT8)_23") (pintype "bidirectional"))
    )
    (net (code "91") (name "RESET1") (class "Default")
      (node (ref "MCU-C1") (pin "1") (pinfunction "PC6(PCINT14/RESET)_1") (pintype "bidirectional"))
      (node (ref "R3") (pin "2") (pinfunction "2_2") (pintype "passive"))
    )
    (net (code "92") (name "RESET2") (class "Default")
      (node (ref "MCU-C2") (pin "1") (pinfunction "PC6(PCINT14/RESET)_1") (pintype "bidirectional"))
      (node (ref "R4") (pin "2") (pinfunction "2_2") (pintype "passive"))
    )
    (net (code "93") (name "RESET3") (class "Default")
      (node (ref "MCU-C3") (pin "1") (pinfunction "PC6(PCINT14/RESET)_1") (pintype "bidirectional"))
      (node (ref "R5") (pin "2") (pinfunction "2_2") (pintype "passive"))
    )
    (net (code "94") (name "SCK") (class "Default")
      (node (ref "MCU-C1") (pin "19") (pinfunction "PB5(SCK/PCINT5)_19") (pintype "bidirectional"))
      (node (ref "MCU-C2") (pin "19") (pinfunction "PB5(SCK/PCINT5)_19") (pintype "bidirectional"))
      (node (ref "MCU-C3") (pin "19") (pinfunction "PB5(SCK/PCINT5)_19") (pintype "bidirectional"))
      (node (ref "MCU-P1") (pin "19") (pinfunction "PB5(SCK/PCINT5)_19") (pintype "bidirectional"))
    )
    (net (code "95") (name "SCL") (class "Default")
      (node (ref "MCU-C1") (pin "28") (pinfunction "PC5(ADC5/SCL/PCINT13)_28") (pintype "bidirectional"))
      (node (ref "MCU-C2") (pin "28") (pinfunction "PC5(ADC5/SCL/PCINT13)_28") (pintype "bidirectional"))
      (node (ref "MCU-C3") (pin "28") (pinfunction "PC5(ADC5/SCL/PCINT13)_28") (pintype "bidirectional"))
      (node (ref "MCU-P1") (pin "28") (pinfunction "PC5(ADC5/SCL/PCINT13)_28") (pintype "bidirectional"))
      (node (ref "R15") (pin "2") (pinfunction "2_2") (pintype "passive"))
    )
    (net (code "96") (name "SDA") (class "Default")
      (node (ref "MCU-C1") (pin "27") (pinfunction "PC4(ADC4/SDA/PCINT12)_27") (pintype "bidirectional"))
      (node (ref "MCU-C2") (pin "27") (pinfunction "PC4(ADC4/SDA/PCINT12)_27") (pintype "bidirectional"))
      (node (ref "MCU-C3") (pin "27") (pinfunction "PC4(ADC4/SDA/PCINT12)_27") (pintype "bidirectional"))
      (node (ref "MCU-P1") (pin "27") (pinfunction "PC4(ADC4/SDA/PCINT12)_27") (pintype "bidirectional"))
      (node (ref "R16") (pin "2") (pinfunction "2_2") (pintype "passive"))
    )
    (net (code "97") (name "TRANSMIT_BUTTON") (class "Default")
      (node (ref "MCU-P1") (pin "5") (pinfunction "PD3(PCINT19/OC2B/INT1)_5") (pintype "bidirectional"))
      (node (ref "TRANSMIT_BUTTON") (pin "3") (pinfunction "3_3") (pintype "passive"))
    )
    (net (code "98") (name "VCC_ARDUINO") (class "Default")
      (node (ref "5V_REG") (pin "OUT") (pinfunction "OUT_OUT") (pintype "passive"))
      (node (ref "8B_INPUT_DIP") (pin "+") (pinfunction "+_+") (pintype "bidirectional"))
      (node (ref "C11") (pin "1") (pinfunction "1_1") (pintype "passive"))
      (node (ref "C12") (pin "1") (pinfunction "1_1") (pintype "passive"))
      (node (ref "C13") (pin "1") (pinfunction "1_1") (pintype "passive"))
      (node (ref "C14") (pin "1") (pinfunction "1_1") (pintype "passive"))
      (node (ref "C15") (pin "1") (pinfunction "1_1") (pintype "passive"))
      (node (ref "C16") (pin "1") (pinfunction "1_1") (pintype "passive"))
      (node (ref "C17") (pin "1") (pinfunction "1_1") (pintype "passive"))
      (node (ref "C18") (pin "1") (pinfunction "1_1") (pintype "passive"))
      (node (ref "C1_POT") (pin "P$1") (pinfunction "P$1_P$1") (pintype "bidirectional"))
      (node (ref "C2_POT") (pin "P$1") (pinfunction "P$1_P$1") (pintype "bidirectional"))
      (node (ref "C3") (pin "1") (pinfunction "1_1") (pintype "passive"))
      (node (ref "C3_POT") (pin "P$1") (pinfunction "P$1_P$1") (pintype "bidirectional"))
      (node (ref "CHIP_SELECT_DIP") (pin "+") (pinfunction "+_+") (pintype "bidirectional"))
      (node (ref "COM_SELECT_DIP") (pin "+") (pinfunction "+_+") (pintype "bidirectional"))
      (node (ref "MCU-C1") (pin "20") (pinfunction "AVCC_20") (pintype "bidirectional"))
      (node (ref "MCU-C1") (pin "21") (pinfunction "AREF_21") (pintype "bidirectional"))
      (node (ref "MCU-C1") (pin "7") (pinfunction "VCC_7") (pintype "bidirectional"))
      (node (ref "MCU-C2") (pin "20") (pinfunction "AVCC_20") (pintype "bidirectional"))
      (node (ref "MCU-C2") (pin "21") (pinfunction "AREF_21") (pintype "bidirectional"))
      (node (ref "MCU-C2") (pin "7") (pinfunction "VCC_7") (pintype "bidirectional"))
      (node (ref "MCU-C3") (pin "20") (pinfunction "AVCC_20") (pintype "bidirectional"))
      (node (ref "MCU-C3") (pin "21") (pinfunction "AREF_21") (pintype "bidirectional"))
      (node (ref "MCU-C3") (pin "7") (pinfunction "VCC_7") (pintype "bidirectional"))
      (node (ref "MCU-P1") (pin "20") (pinfunction "AVCC_20") (pintype "bidirectional"))
      (node (ref "MCU-P1") (pin "21") (pinfunction "AREF_21") (pintype "bidirectional"))
      (node (ref "MCU-P1") (pin "7") (pinfunction "VCC_7") (pintype "bidirectional"))
      (node (ref "P1_POT") (pin "P$1") (pinfunction "P$1_P$1") (pintype "bidirectional"))
      (node (ref "R1") (pin "1") (pinfunction "1_1") (pintype "passive"))
      (node (ref "R15") (pin "1") (pinfunction "1_1") (pintype "passive"))
      (node (ref "R16") (pin "1") (pinfunction "1_1") (pintype "passive"))
      (node (ref "R2") (pin "1") (pinfunction "1_1") (pintype "passive"))
      (node (ref "R3") (pin "1") (pinfunction "1_1") (pintype "passive"))
      (node (ref "R4") (pin "1") (pinfunction "1_1") (pintype "passive"))
      (node (ref "R5") (pin "1") (pinfunction "1_1") (pintype "passive"))
      (node (ref "SHIFT_REG_C1") (pin "7") (pinfunction "7_7") (pintype "passive"))
      (node (ref "SHIFT_REG_C2") (pin "7") (pinfunction "7_7") (pintype "passive"))
      (node (ref "SHIFT_REG_C3") (pin "7") (pinfunction "7_7") (pintype "passive"))
      (node (ref "SHIFT_REG_P1") (pin "7") (pinfunction "7_7") (pintype "passive"))
    )
    (net (code "99") (name "VOLTAGE_INPUT") (class "Default")
      (node (ref "5V_REG") (pin "IN") (pinfunction "IN_IN") (pintype "input"))
      (node (ref "C2") (pin "1") (pinfunction "1_1") (pintype "passive"))
      (node (ref "INPUT") (pin "1") (pinfunction "1_1") (pintype "passive"))
    )
    (net (code "100") (name "unconnected-(8B_INPUT_R2R-Pad9)") (class "Default")
      (node (ref "8B_INPUT_R2R") (pin "9") (pinfunction "9_9") (pintype "bidirectional"))
    )
    (net (code "101") (name "unconnected-(8B_INPUT_R2R-Pad10)") (class "Default")
      (node (ref "8B_INPUT_R2R") (pin "10") (pinfunction "10_10") (pintype "bidirectional"))
    )
    (net (code "102") (name "unconnected-(8B_INPUT_R2R-Pad11)") (class "Default")
      (node (ref "8B_INPUT_R2R") (pin "11") (pinfunction "11_11") (pintype "bidirectional"))
    )
    (net (code "103") (name "unconnected-(8B_INPUT_R2R-Pad12)") (class "Default")
      (node (ref "8B_INPUT_R2R") (pin "12") (pinfunction "12_12") (pintype "bidirectional"))
    )
    (net (code "104") (name "unconnected-(8B_INPUT_R2R-Pad13)") (class "Default")
      (node (ref "8B_INPUT_R2R") (pin "13") (pinfunction "13_13") (pintype "bidirectional"))
    )
    (net (code "105") (name "unconnected-(8B_INPUT_R2R-Pad14)") (class "Default")
      (node (ref "8B_INPUT_R2R") (pin "14") (pinfunction "14_14") (pintype "bidirectional"))
    )
    (net (code "106") (name "unconnected-(8B_INPUT_R2R-Pad15)") (class "Default")
      (node (ref "8B_INPUT_R2R") (pin "15") (pinfunction "15_15") (pintype "bidirectional"))
    )
    (net (code "107") (name "unconnected-(CHIP_SELECT_R2R-Pad9)") (class "Default")
      (node (ref "CHIP_SELECT_R2R") (pin "9") (pinfunction "9_9") (pintype "bidirectional"))
    )
    (net (code "108") (name "unconnected-(CHIP_SELECT_R2R-Pad10)") (class "Default")
      (node (ref "CHIP_SELECT_R2R") (pin "10") (pinfunction "10_10") (pintype "bidirectional"))
    )
    (net (code "109") (name "unconnected-(CHIP_SELECT_R2R-Pad11)") (class "Default")
      (node (ref "CHIP_SELECT_R2R") (pin "11") (pinfunction "11_11") (pintype "bidirectional"))
    )
    (net (code "110") (name "unconnected-(CHIP_SELECT_R2R-Pad12)") (class "Default")
      (node (ref "CHIP_SELECT_R2R") (pin "12") (pinfunction "12_12") (pintype "bidirectional"))
    )
    (net (code "111") (name "unconnected-(CHIP_SELECT_R2R-Pad13)") (class "Default")
      (node (ref "CHIP_SELECT_R2R") (pin "13") (pinfunction "13_13") (pintype "bidirectional"))
    )
    (net (code "112") (name "unconnected-(CHIP_SELECT_R2R-Pad14)") (class "Default")
      (node (ref "CHIP_SELECT_R2R") (pin "14") (pinfunction "14_14") (pintype "bidirectional"))
    )
    (net (code "113") (name "unconnected-(CHIP_SELECT_R2R-Pad15)") (class "Default")
      (node (ref "CHIP_SELECT_R2R") (pin "15") (pinfunction "15_15") (pintype "bidirectional"))
    )
    (net (code "114") (name "unconnected-(COM_SELECT_R2R-Pad9)") (class "Default")
      (node (ref "COM_SELECT_R2R") (pin "9") (pinfunction "9_9") (pintype "bidirectional"))
    )
    (net (code "115") (name "unconnected-(COM_SELECT_R2R-Pad10)") (class "Default")
      (node (ref "COM_SELECT_R2R") (pin "10") (pinfunction "10_10") (pintype "bidirectional"))
    )
    (net (code "116") (name "unconnected-(COM_SELECT_R2R-Pad11)") (class "Default")
      (node (ref "COM_SELECT_R2R") (pin "11") (pinfunction "11_11") (pintype "bidirectional"))
    )
    (net (code "117") (name "unconnected-(COM_SELECT_R2R-Pad12)") (class "Default")
      (node (ref "COM_SELECT_R2R") (pin "12") (pinfunction "12_12") (pintype "bidirectional"))
    )
    (net (code "118") (name "unconnected-(COM_SELECT_R2R-Pad13)") (class "Default")
      (node (ref "COM_SELECT_R2R") (pin "13") (pinfunction "13_13") (pintype "bidirectional"))
    )
    (net (code "119") (name "unconnected-(COM_SELECT_R2R-Pad14)") (class "Default")
      (node (ref "COM_SELECT_R2R") (pin "14") (pinfunction "14_14") (pintype "bidirectional"))
    )
    (net (code "120") (name "unconnected-(COM_SELECT_R2R-Pad15)") (class "Default")
      (node (ref "COM_SELECT_R2R") (pin "15") (pinfunction "15_15") (pintype "bidirectional"))
    )
    (net (code "121") (name "unconnected-(MCU-C1-PB0(PCINT0{slash}CLKO{slash}ICP1)-Pad14)") (class "Default")
      (node (ref "MCU-C1") (pin "14") (pinfunction "PB0(PCINT0/CLKO/ICP1)_14") (pintype "bidirectional"))
    )
    (net (code "122") (name "unconnected-(MCU-C1-PB1(OC1A{slash}PCINT1)-Pad15)") (class "Default")
      (node (ref "MCU-C1") (pin "15") (pinfunction "PB1(OC1A/PCINT1)_15") (pintype "bidirectional"))
    )
    (net (code "123") (name "unconnected-(MCU-C1-PC0(ADC0{slash}PCINT8)-Pad23)") (class "Default")
      (node (ref "MCU-C1") (pin "23") (pinfunction "PC0(ADC0/PCINT8)_23") (pintype "bidirectional"))
    )
    (net (code "124") (name "unconnected-(MCU-C1-PC1(ADC1{slash}PCINT9)-Pad24)") (class "Default")
      (node (ref "MCU-C1") (pin "24") (pinfunction "PC1(ADC1/PCINT9)_24") (pintype "bidirectional"))
    )
    (net (code "125") (name "unconnected-(MCU-C1-PC2(ADC2{slash}PCINT10)-Pad25)") (class "Default")
      (node (ref "MCU-C1") (pin "25") (pinfunction "PC2(ADC2/PCINT10)_25") (pintype "bidirectional"))
    )
    (net (code "126") (name "unconnected-(MCU-C2-PB1(OC1A{slash}PCINT1)-Pad15)") (class "Default")
      (node (ref "MCU-C2") (pin "15") (pinfunction "PB1(OC1A/PCINT1)_15") (pintype "bidirectional"))
    )
    (net (code "127") (name "unconnected-(MCU-C2-PC0(ADC0{slash}PCINT8)-Pad23)") (class "Default")
      (node (ref "MCU-C2") (pin "23") (pinfunction "PC0(ADC0/PCINT8)_23") (pintype "bidirectional"))
    )
    (net (code "128") (name "unconnected-(MCU-C2-PC1(ADC1{slash}PCINT9)-Pad24)") (class "Default")
      (node (ref "MCU-C2") (pin "24") (pinfunction "PC1(ADC1/PCINT9)_24") (pintype "bidirectional"))
    )
    (net (code "129") (name "unconnected-(MCU-C2-PC2(ADC2{slash}PCINT10)-Pad25)") (class "Default")
      (node (ref "MCU-C2") (pin "25") (pinfunction "PC2(ADC2/PCINT10)_25") (pintype "bidirectional"))
    )
    (net (code "130") (name "unconnected-(MCU-C3-PB1(OC1A{slash}PCINT1)-Pad15)") (class "Default")
      (node (ref "MCU-C3") (pin "15") (pinfunction "PB1(OC1A/PCINT1)_15") (pintype "bidirectional"))
    )
    (net (code "131") (name "unconnected-(MCU-C3-PC0(ADC0{slash}PCINT8)-Pad23)") (class "Default")
      (node (ref "MCU-C3") (pin "23") (pinfunction "PC0(ADC0/PCINT8)_23") (pintype "bidirectional"))
    )
    (net (code "132") (name "unconnected-(MCU-C3-PC1(ADC1{slash}PCINT9)-Pad24)") (class "Default")
      (node (ref "MCU-C3") (pin "24") (pinfunction "PC1(ADC1/PCINT9)_24") (pintype "bidirectional"))
    )
    (net (code "133") (name "unconnected-(MCU-C3-PC2(ADC2{slash}PCINT10)-Pad25)") (class "Default")
      (node (ref "MCU-C3") (pin "25") (pinfunction "PC2(ADC2/PCINT10)_25") (pintype "bidirectional"))
    )
    (net (code "134") (name "unconnected-(RESET_BUTTON-Pad2)") (class "Default")
      (node (ref "RESET_BUTTON") (pin "2") (pinfunction "2_2") (pintype "passive"))
    )
    (net (code "135") (name "unconnected-(RESET_BUTTON-Pad4)") (class "Default")
      (node (ref "RESET_BUTTON") (pin "4") (pinfunction "4_4") (pintype "passive"))
    )
    (net (code "136") (name "unconnected-(SHIFT_REG_C1-Pad6)") (class "Default")
      (node (ref "SHIFT_REG_C1") (pin "6") (pinfunction "6_6") (pintype "passive"))
    )
    (net (code "137") (name "unconnected-(SHIFT_REG_C2-Pad6)") (class "Default")
      (node (ref "SHIFT_REG_C2") (pin "6") (pinfunction "6_6") (pintype "passive"))
    )
    (net (code "138") (name "unconnected-(SHIFT_REG_C3-Pad6)") (class "Default")
      (node (ref "SHIFT_REG_C3") (pin "6") (pinfunction "6_6") (pintype "passive"))
    )
    (net (code "139") (name "unconnected-(SHIFT_REG_P1-Pad6)") (class "Default")
      (node (ref "SHIFT_REG_P1") (pin "6") (pinfunction "6_6") (pintype "passive"))
    )
    (net (code "140") (name "unconnected-(TRANSMIT_BUTTON-Pad2)") (class "Default")
      (node (ref "TRANSMIT_BUTTON") (pin "2") (pinfunction "2_2") (pintype "passive"))
    )
    (net (code "141") (name "unconnected-(TRANSMIT_BUTTON-Pad4)") (class "Default")
      (node (ref "TRANSMIT_BUTTON") (pin "4") (pinfunction "4_4") (pintype "passive"))
    )
  )
)
